# dev_kit.net
KiCad netlist of a schematic drawn in EasyEDA
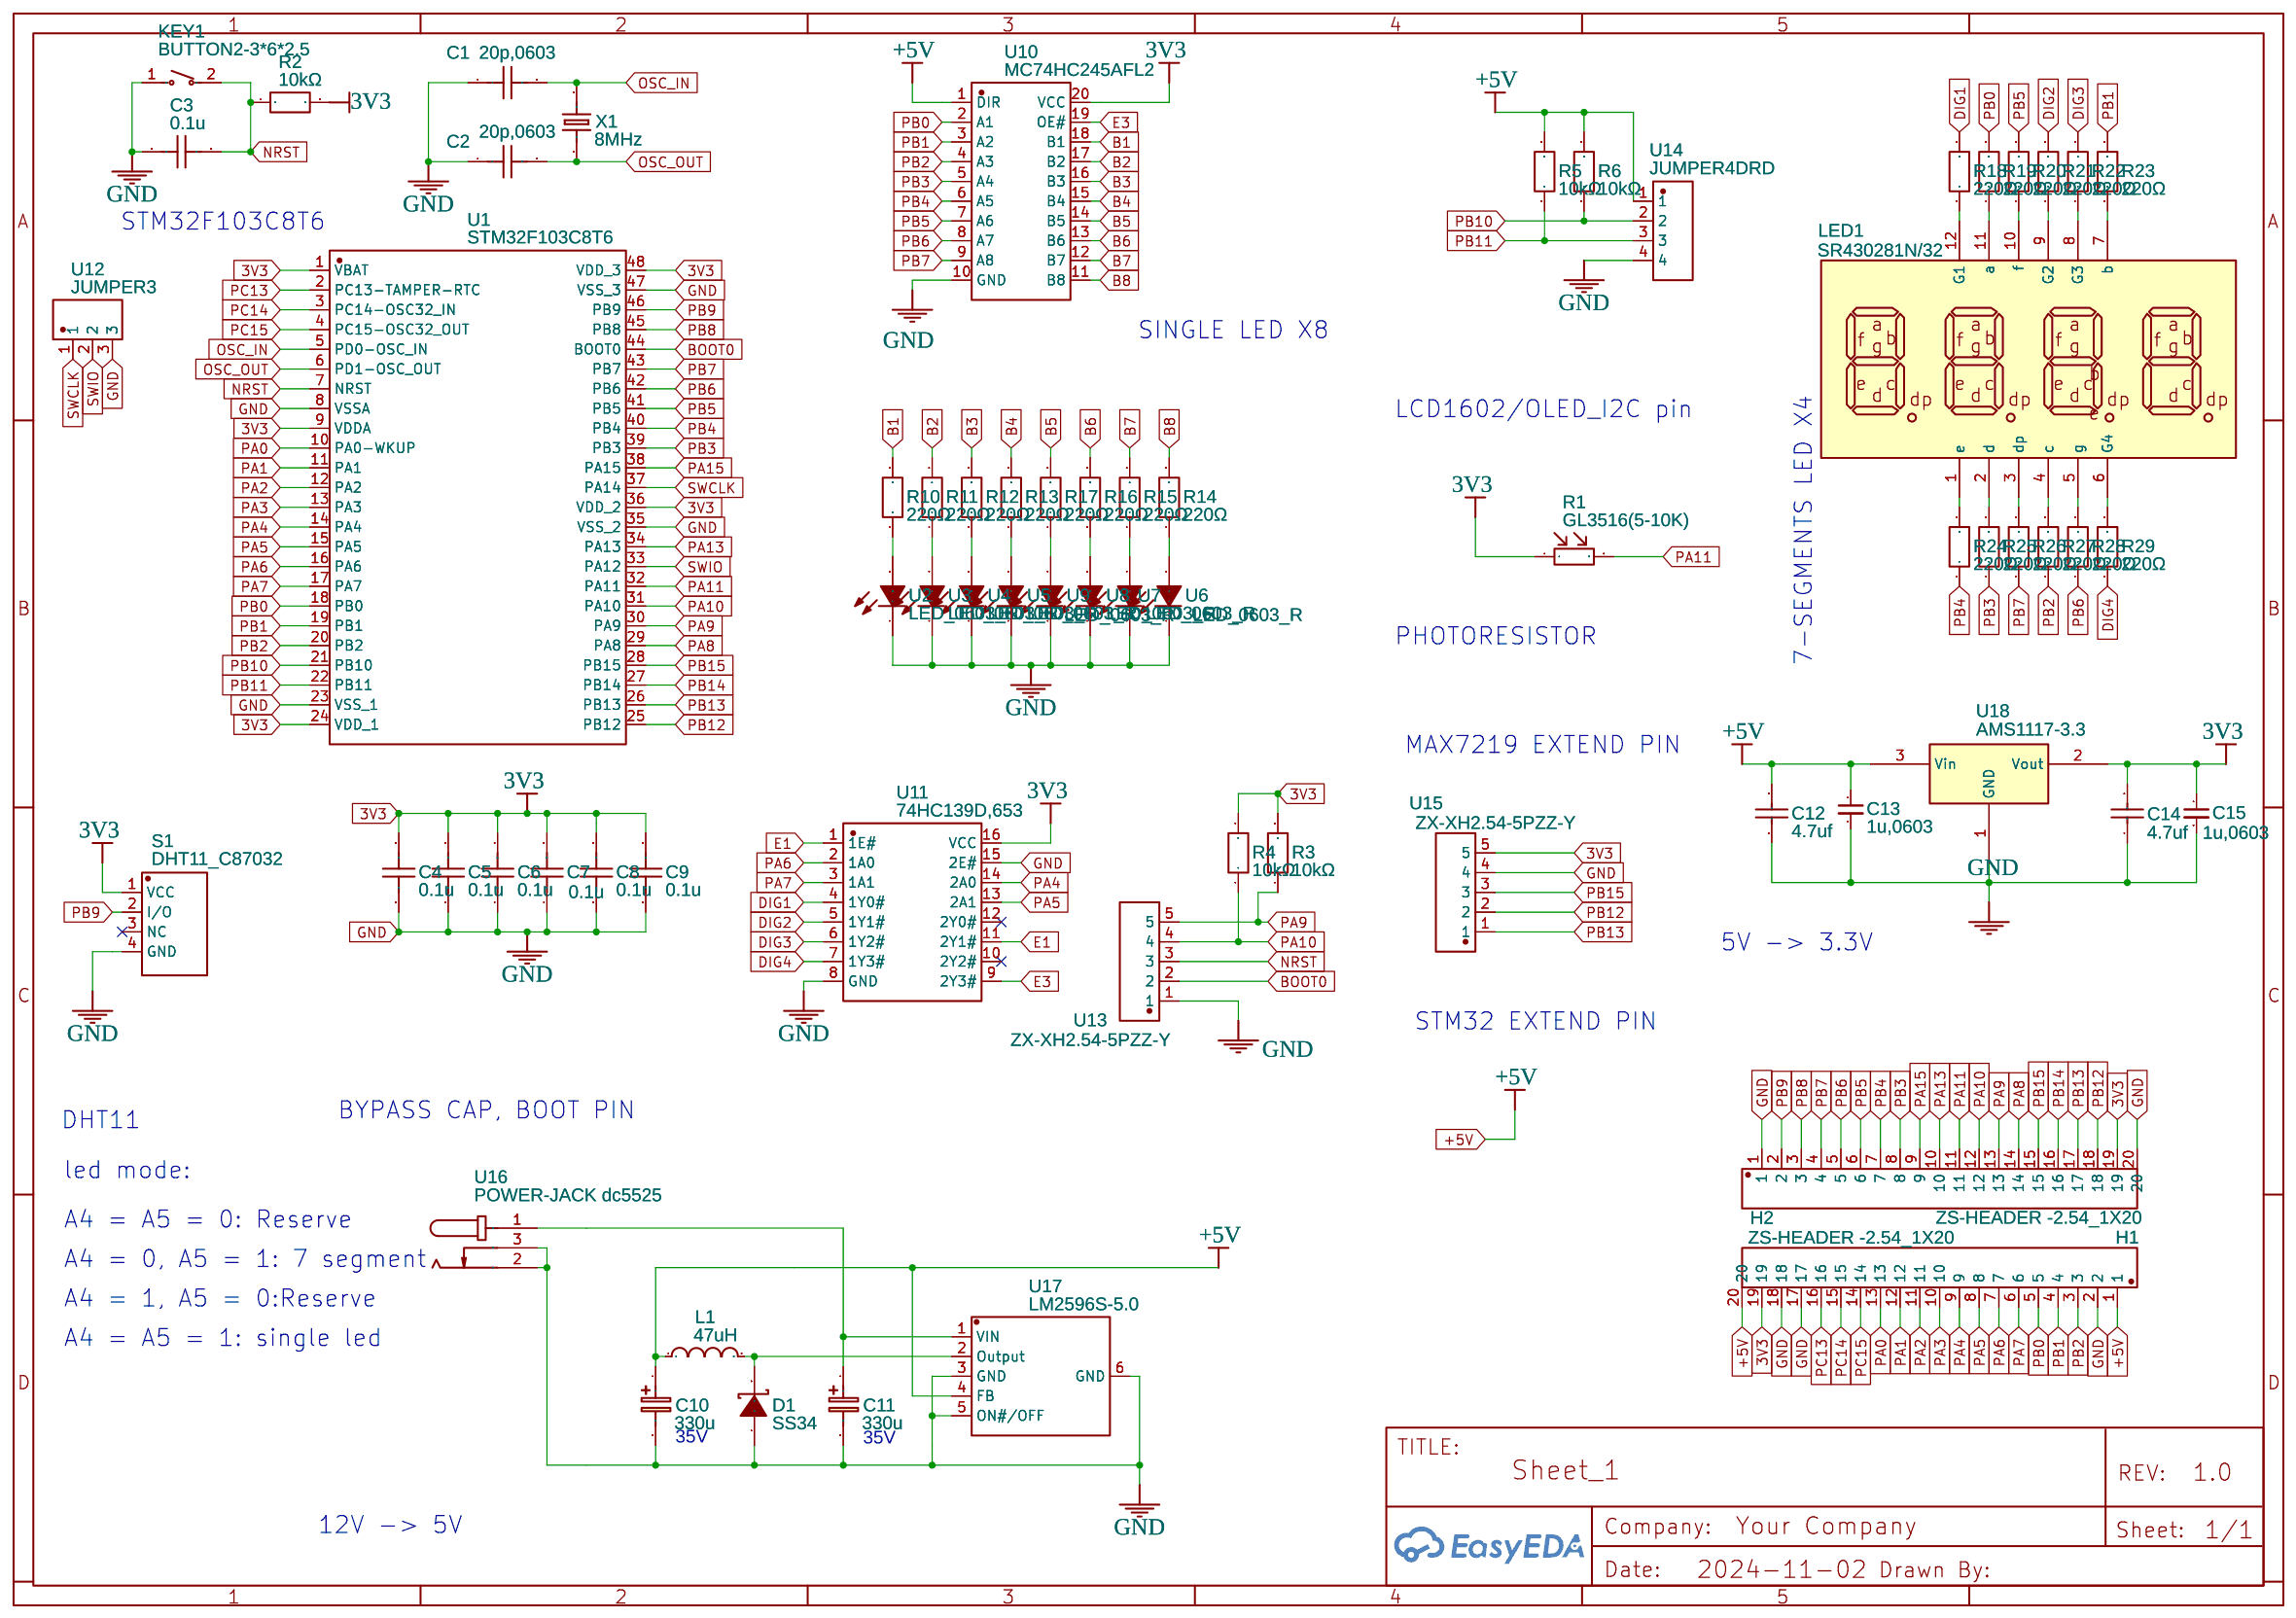
[diagram p0: schematic sheet]

(export (version "E")
  (design (tool "Eeschema 10.0.6"))
  (components
    (comp (ref "C1") (value "20p,0603") (libsource (lib "") (part "C_0603_US_1")))
    (comp (ref "C2") (value "20p,0603") (libsource (lib "") (part "C_0603_US_1")))
    (comp (ref "C3") (value "0.1u") (libsource (lib "") (part "C_0603_US_1")))
    (comp (ref "C4") (value "0.1u") (libsource (lib "") (part "C_0603_US")))
    (comp (ref "C5") (value "0.1u") (libsource (lib "") (part "C_0603_US")))
    (comp (ref "C6") (value "0.1u") (libsource (lib "") (part "C_0603_US")))
    (comp (ref "C7") (value "0.1u") (libsource (lib "") (part "C_0603_US")))
    (comp (ref "C8") (value "0.1u") (libsource (lib "") (part "C_0603_US")))
    (comp (ref "C9") (value "0.1u") (libsource (lib "") (part "C_0603_US")))
    (comp (ref "C10")
      (value "330u")
      (fields (field (name "Manufacturer Part") "?"))
      (libsource (lib "") (part "Cap_Electrolytic(SMD)_D8.0XH10.5_EU"))
    )
    (comp (ref "C11")
      (value "330u")
      (fields (field (name "Manufacturer Part") "?"))
      (libsource (lib "") (part "Cap_Electrolytic(SMD)_D8.0XH10.5_EU"))
    )
    (comp (ref "C12")
      (value "4.7uf")
      (fields (field (name "Manufacturer Part") "?"))
      (libsource (lib "") (part "Unknown_890_-400"))
    )
    (comp (ref "C13") (value "1u,0603") (libsource (lib "") (part "C_0603")))
    (comp (ref "C14")
      (value "4.7uf")
      (fields (field (name "Manufacturer Part") "?"))
      (libsource (lib "") (part "Unknown_1070_-400"))
    )
    (comp (ref "C15") (value "1u,0603") (libsource (lib "") (part "C_0603")))
    (comp (ref "D1")
      (value "SS34")
      (fields (field (name "Manufacturer") "Yenji"))
      (libsource (lib "") (part "Unknown_375_-105"))
    )
    (comp (ref "H1") (value "ZS-HEADER -2.54_1X20") (libsource (lib "") (part "ZS-HEADER -2.54_1X20")))
    (comp (ref "H2") (value "ZS-HEADER -2.54_1X20") (libsource (lib "") (part "ZS-HEADER -2.54_1X20_1")))
    (comp (ref "KEY1") (value "BUTTON2-3*6*2.5") (libsource (lib "") (part "BUTTON2-3*6*2.5")))
    (comp (ref "L1")
      (value "47uH")
      (fields (field (name "Manufacturer Part") "CDRH127NP-470MC") (field (name "Manufacturer") "Sumida"))
      (libsource (lib "") (part "CDRH127NP-470MC"))
    )
    (comp (ref "LED1")
      (value "SR430281N/32")
      (fields (field (name "Manufacturer") "ARKLED(方舟)"))
      (libsource (lib "") (part "SR430281N/32"))
    )
    (comp (ref "R1")
      (value "GL3516(5-10K)")
      (fields (field (name "Manufacturer Part") "GL3516（5-10K）") (field (name "Manufacturer") "JCHL(晶创和立)"))
      (libsource (lib "") (part "GL3516(5-10K)"))
    )
    (comp (ref "R2")
      (value "10kΩ")
      (fields (field (name "Manufacturer Part") "TD03E1002BT") (field (name "Manufacturer") "FH(风华)"))
      (libsource (lib "") (part "TD03E1002BT_1"))
    )
    (comp (ref "R3")
      (value "10kΩ")
      (fields (field (name "Manufacturer Part") "TD03E1002BT") (field (name "Manufacturer") "FH(风华)"))
      (libsource (lib "") (part "TD03E1002BT"))
    )
    (comp (ref "R4")
      (value "10kΩ")
      (fields (field (name "Manufacturer Part") "TD03E1002BT") (field (name "Manufacturer") "FH(风华)"))
      (libsource (lib "") (part "TD03E1002BT"))
    )
    (comp (ref "R5")
      (value "10kΩ")
      (fields (field (name "Manufacturer Part") "TD03E1002BT") (field (name "Manufacturer") "FH(风华)"))
      (libsource (lib "") (part "TD03E1002BT"))
    )
    (comp (ref "R6")
      (value "10kΩ")
      (fields (field (name "Manufacturer Part") "TD03E1002BT") (field (name "Manufacturer") "FH(风华)"))
      (libsource (lib "") (part "TD03E1002BT"))
    )
    (comp (ref "R10")
      (value "220Ω")
      (fields
        (field (name "Manufacturer Part") "CRCW0603220RFKEA")
        (field (name "Manufacturer") "VISHAY(威世)")
      )
      (libsource (lib "") (part "CRCW0603220RFKEA"))
    )
    (comp (ref "R11")
      (value "220Ω")
      (fields
        (field (name "Manufacturer Part") "CRCW0603220RFKEA")
        (field (name "Manufacturer") "VISHAY(威世)")
      )
      (libsource (lib "") (part "CRCW0603220RFKEA"))
    )
    (comp (ref "R12")
      (value "220Ω")
      (fields
        (field (name "Manufacturer Part") "CRCW0603220RFKEA")
        (field (name "Manufacturer") "VISHAY(威世)")
      )
      (libsource (lib "") (part "CRCW0603220RFKEA"))
    )
    (comp (ref "R13")
      (value "220Ω")
      (fields
        (field (name "Manufacturer Part") "CRCW0603220RFKEA")
        (field (name "Manufacturer") "VISHAY(威世)")
      )
      (libsource (lib "") (part "CRCW0603220RFKEA"))
    )
    (comp (ref "R14")
      (value "220Ω")
      (fields
        (field (name "Manufacturer Part") "CRCW0603220RFKEA")
        (field (name "Manufacturer") "VISHAY(威世)")
      )
      (libsource (lib "") (part "CRCW0603220RFKEA"))
    )
    (comp (ref "R15")
      (value "220Ω")
      (fields
        (field (name "Manufacturer Part") "CRCW0603220RFKEA")
        (field (name "Manufacturer") "VISHAY(威世)")
      )
      (libsource (lib "") (part "CRCW0603220RFKEA"))
    )
    (comp (ref "R16")
      (value "220Ω")
      (fields
        (field (name "Manufacturer Part") "CRCW0603220RFKEA")
        (field (name "Manufacturer") "VISHAY(威世)")
      )
      (libsource (lib "") (part "CRCW0603220RFKEA"))
    )
    (comp (ref "R17")
      (value "220Ω")
      (fields
        (field (name "Manufacturer Part") "CRCW0603220RFKEA")
        (field (name "Manufacturer") "VISHAY(威世)")
      )
      (libsource (lib "") (part "CRCW0603220RFKEA"))
    )
    (comp (ref "R18")
      (value "220Ω")
      (fields
        (field (name "Manufacturer Part") "CRCW0603220RFKEA")
        (field (name "Manufacturer") "VISHAY(威世)")
      )
      (libsource (lib "") (part "CRCW0603220RFKEA"))
    )
    (comp (ref "R19")
      (value "220Ω")
      (fields
        (field (name "Manufacturer Part") "CRCW0603220RFKEA")
        (field (name "Manufacturer") "VISHAY(威世)")
      )
      (libsource (lib "") (part "CRCW0603220RFKEA"))
    )
    (comp (ref "R20")
      (value "220Ω")
      (fields
        (field (name "Manufacturer Part") "CRCW0603220RFKEA")
        (field (name "Manufacturer") "VISHAY(威世)")
      )
      (libsource (lib "") (part "CRCW0603220RFKEA"))
    )
    (comp (ref "R21")
      (value "220Ω")
      (fields
        (field (name "Manufacturer Part") "CRCW0603220RFKEA")
        (field (name "Manufacturer") "VISHAY(威世)")
      )
      (libsource (lib "") (part "CRCW0603220RFKEA"))
    )
    (comp (ref "R22")
      (value "220Ω")
      (fields
        (field (name "Manufacturer Part") "CRCW0603220RFKEA")
        (field (name "Manufacturer") "VISHAY(威世)")
      )
      (libsource (lib "") (part "CRCW0603220RFKEA"))
    )
    (comp (ref "R23")
      (value "220Ω")
      (fields
        (field (name "Manufacturer Part") "CRCW0603220RFKEA")
        (field (name "Manufacturer") "VISHAY(威世)")
      )
      (libsource (lib "") (part "CRCW0603220RFKEA"))
    )
    (comp (ref "R24")
      (value "220Ω")
      (fields
        (field (name "Manufacturer Part") "CRCW0603220RFKEA")
        (field (name "Manufacturer") "VISHAY(威世)")
      )
      (libsource (lib "") (part "CRCW0603220RFKEA"))
    )
    (comp (ref "R25")
      (value "220Ω")
      (fields
        (field (name "Manufacturer Part") "CRCW0603220RFKEA")
        (field (name "Manufacturer") "VISHAY(威世)")
      )
      (libsource (lib "") (part "CRCW0603220RFKEA"))
    )
    (comp (ref "R26")
      (value "220Ω")
      (fields
        (field (name "Manufacturer Part") "CRCW0603220RFKEA")
        (field (name "Manufacturer") "VISHAY(威世)")
      )
      (libsource (lib "") (part "CRCW0603220RFKEA"))
    )
    (comp (ref "R27")
      (value "220Ω")
      (fields
        (field (name "Manufacturer Part") "CRCW0603220RFKEA")
        (field (name "Manufacturer") "VISHAY(威世)")
      )
      (libsource (lib "") (part "CRCW0603220RFKEA"))
    )
    (comp (ref "R28")
      (value "220Ω")
      (fields
        (field (name "Manufacturer Part") "CRCW0603220RFKEA")
        (field (name "Manufacturer") "VISHAY(威世)")
      )
      (libsource (lib "") (part "CRCW0603220RFKEA"))
    )
    (comp (ref "R29")
      (value "220Ω")
      (fields
        (field (name "Manufacturer Part") "CRCW0603220RFKEA")
        (field (name "Manufacturer") "VISHAY(威世)")
      )
      (libsource (lib "") (part "CRCW0603220RFKEA"))
    )
    (comp (ref "S1")
      (value "DHT11_C87032")
      (fields (field (name "Manufacturer Part") "DHT11") (field (name "Manufacturer") "AOSONG"))
      (libsource (lib "") (part "DHT11_C87032"))
    )
    (comp (ref "U1")
      (value "STM32F103C8T6")
      (fields (field (name "Manufacturer") "ST(意法半导体)"))
      (libsource (lib "") (part "STM32F103C8T6"))
    )
    (comp (ref "U2") (value "LED_0603_R") (libsource (lib "") (part "LED_0603_R")))
    (comp (ref "U3") (value "LED_0603_R") (libsource (lib "") (part "LED_0603_R")))
    (comp (ref "U4") (value "LED_0603_R") (libsource (lib "") (part "LED_0603_R")))
    (comp (ref "U5") (value "LED_0603_R") (libsource (lib "") (part "LED_0603_R")))
    (comp (ref "U6") (value "LED_0603_R") (libsource (lib "") (part "LED_0603_R")))
    (comp (ref "U7") (value "LED_0603_R") (libsource (lib "") (part "LED_0603_R")))
    (comp (ref "U8") (value "LED_0603_R") (libsource (lib "") (part "LED_0603_R")))
    (comp (ref "U9") (value "LED_0603_R") (libsource (lib "") (part "LED_0603_R")))
    (comp (ref "U10")
      (value "MC74HC245AFL2")
      (fields (field (name "Manufacturer") "MOTOROLA(摩托罗拉)"))
      (libsource (lib "") (part "MC74HC245AFL2"))
    )
    (comp (ref "U11")
      (value "74HC139D,653")
      (fields (field (name "Manufacturer") "Nexperia(安世)"))
      (libsource (lib "") (part "74HC139D,653"))
    )
    (comp (ref "U12")
      (value "JUMPER3")
      (fields (field (name "Manufacturer Part") "Jumper3"))
      (libsource (lib "") (part "JUMPER3"))
    )
    (comp (ref "U13")
      (value "ZX-XH2.54-5PZZ-Y")
      (fields (field (name "Manufacturer") "Megastar(兆星)"))
      (libsource (lib "") (part "ZX-XH2.54-5PZZ-Y"))
    )
    (comp (ref "U14")
      (value "JUMPER4DRD")
      (fields (field (name "Manufacturer Part") "Jumper4"))
      (libsource (lib "") (part "JUMPER4DRD"))
    )
    (comp (ref "U15")
      (value "ZX-XH2.54-5PZZ-Y")
      (fields (field (name "Manufacturer") "Megastar(兆星)"))
      (libsource (lib "") (part "ZX-XH2.54-5PZZ-Y"))
    )
    (comp (ref "U16")
      (value "POWER-JACK dc5525")
      (fields (field (name "Manufacturer Part") "POWER-JACK"))
      (libsource (lib "") (part "POWER-JACK dc5525"))
    )
    (comp (ref "U17")
      (value "LM2596S-5.0")
      (fields
        (field (name "Manufacturer Part") "LM2596S-5.0/NOPB")
        (field (name "Manufacturer") "Texas Instruments")
      )
      (libsource (lib "") (part "Unknown_520_-120"))
    )
    (comp (ref "U18")
      (value "AMS1117-3.3")
      (fields (field (name "Manufacturer Part") "?"))
      (libsource (lib "") (part "Unknown_1000_-420"))
    )
    (comp (ref "X1")
      (value "8MHz")
      (fields
        (field (name "Manufacturer Part") "49S-8.00-20-10-10/A")
        (field (name "Manufacturer") "LIMING(利明)")
      )
      (libsource (lib "") (part "49S-8.00-20-10-10/A"))
    )
  )
  (nets
    (net (code "1") (name "+5V") (class "Default")
      (node (ref "C10") (pin "1") (pinfunction "1_1") (pintype "unspecified"))
      (node (ref "C12") (pin "2") (pinfunction "2_2") (pintype "unspecified"))
      (node (ref "C13") (pin "1") (pintype "unspecified"))
      (node (ref "H2") (pin "1") (pinfunction "1_1") (pintype "unspecified"))
      (node (ref "H2") (pin "20") (pinfunction "20_20") (pintype "unspecified"))
      (node (ref "L1") (pin "1") (pinfunction "1_1") (pintype "unspecified"))
      (node (ref "R5") (pin "2") (pinfunction "2_2") (pintype "unspecified"))
      (node (ref "R6") (pin "2") (pinfunction "2_2") (pintype "unspecified"))
      (node (ref "U10") (pin "1") (pinfunction "DIR_1") (pintype "unspecified"))
      (node (ref "U14") (pin "1") (pinfunction "1_1") (pintype "unspecified"))
      (node (ref "U17") (pin "4") (pinfunction "FB_4") (pintype "unspecified"))
      (node (ref "U18") (pin "3") (pinfunction "Vin_3") (pintype "unspecified"))
    )
    (net (code "2") (name "3V3") (class "Default")
      (node (ref "C14") (pin "2") (pinfunction "2_2") (pintype "unspecified"))
      (node (ref "C15") (pin "1") (pintype "unspecified"))
      (node (ref "C4") (pin "2") (pinfunction "2_2") (pintype "unspecified"))
      (node (ref "C5") (pin "2") (pinfunction "2_2") (pintype "unspecified"))
      (node (ref "C6") (pin "2") (pinfunction "2_2") (pintype "unspecified"))
      (node (ref "C7") (pin "2") (pinfunction "2_2") (pintype "unspecified"))
      (node (ref "C8") (pin "2") (pinfunction "2_2") (pintype "unspecified"))
      (node (ref "C9") (pin "2") (pinfunction "2_2") (pintype "unspecified"))
      (node (ref "H1") (pin "19") (pinfunction "19_19") (pintype "unspecified"))
      (node (ref "H2") (pin "19") (pinfunction "19_19") (pintype "unspecified"))
      (node (ref "R1") (pin "1") (pinfunction "1_1") (pintype "input"))
      (node (ref "R2") (pin "2") (pinfunction "2_2") (pintype "unspecified"))
      (node (ref "R3") (pin "2") (pinfunction "2_2") (pintype "unspecified"))
      (node (ref "R4") (pin "2") (pinfunction "2_2") (pintype "unspecified"))
      (node (ref "S1") (pin "1") (pinfunction "VCC_1") (pintype "unspecified"))
      (node (ref "U1") (pin "1") (pinfunction "VBAT_1") (pintype "unspecified"))
      (node (ref "U1") (pin "24") (pinfunction "VDD_1_24") (pintype "unspecified"))
      (node (ref "U1") (pin "36") (pinfunction "VDD_2_36") (pintype "unspecified"))
      (node (ref "U1") (pin "48") (pinfunction "VDD_3_48") (pintype "unspecified"))
      (node (ref "U1") (pin "9") (pinfunction "VDDA_9") (pintype "unspecified"))
      (node (ref "U10") (pin "20") (pinfunction "VCC_20") (pintype "unspecified"))
      (node (ref "U11") (pin "16") (pinfunction "VCC_16") (pintype "unspecified"))
      (node (ref "U15") (pin "5") (pinfunction "5_5") (pintype "unspecified"))
      (node (ref "U18") (pin "2") (pinfunction "Vout_2") (pintype "unspecified"))
    )
    (net (code "3") (name "B1") (class "Default")
      (node (ref "R10") (pin "2") (pinfunction "2_2") (pintype "unspecified"))
      (node (ref "U10") (pin "18") (pinfunction "B1_18") (pintype "unspecified"))
    )
    (net (code "4") (name "B2") (class "Default")
      (node (ref "R11") (pin "2") (pinfunction "2_2") (pintype "unspecified"))
      (node (ref "U10") (pin "17") (pinfunction "B2_17") (pintype "unspecified"))
    )
    (net (code "5") (name "B3") (class "Default")
      (node (ref "R12") (pin "2") (pinfunction "2_2") (pintype "unspecified"))
      (node (ref "U10") (pin "16") (pinfunction "B3_16") (pintype "unspecified"))
    )
    (net (code "6") (name "B4") (class "Default")
      (node (ref "R13") (pin "2") (pinfunction "2_2") (pintype "unspecified"))
      (node (ref "U10") (pin "15") (pinfunction "B4_15") (pintype "unspecified"))
    )
    (net (code "7") (name "B5") (class "Default")
      (node (ref "R17") (pin "2") (pinfunction "2_2") (pintype "unspecified"))
      (node (ref "U10") (pin "14") (pinfunction "B5_14") (pintype "unspecified"))
    )
    (net (code "8") (name "B6") (class "Default")
      (node (ref "R16") (pin "2") (pinfunction "2_2") (pintype "unspecified"))
      (node (ref "U10") (pin "13") (pinfunction "B6_13") (pintype "unspecified"))
    )
    (net (code "9") (name "B7") (class "Default")
      (node (ref "R15") (pin "2") (pinfunction "2_2") (pintype "unspecified"))
      (node (ref "U10") (pin "12") (pinfunction "B7_12") (pintype "unspecified"))
    )
    (net (code "10") (name "B8") (class "Default")
      (node (ref "R14") (pin "2") (pinfunction "2_2") (pintype "unspecified"))
      (node (ref "U10") (pin "11") (pinfunction "B8_11") (pintype "unspecified"))
    )
    (net (code "11") (name "BOOT0") (class "Default")
      (node (ref "U1") (pin "44") (pinfunction "BOOT0_44") (pintype "unspecified"))
      (node (ref "U13") (pin "2") (pinfunction "2_2") (pintype "unspecified"))
    )
    (net (code "12") (name "DIG1") (class "Default")
      (node (ref "R18") (pin "2") (pinfunction "2_2") (pintype "unspecified"))
      (node (ref "U11") (pin "4") (pinfunction "1Y0#_4") (pintype "unspecified"))
    )
    (net (code "13") (name "DIG2") (class "Default")
      (node (ref "R21") (pin "2") (pinfunction "2_2") (pintype "unspecified"))
      (node (ref "U11") (pin "5") (pinfunction "1Y1#_5") (pintype "unspecified"))
    )
    (net (code "14") (name "DIG3") (class "Default")
      (node (ref "R22") (pin "2") (pinfunction "2_2") (pintype "unspecified"))
      (node (ref "U11") (pin "6") (pinfunction "1Y2#_6") (pintype "unspecified"))
    )
    (net (code "15") (name "DIG4") (class "Default")
      (node (ref "R29") (pin "1") (pinfunction "1_1") (pintype "unspecified"))
      (node (ref "U11") (pin "7") (pinfunction "1Y3#_7") (pintype "unspecified"))
    )
    (net (code "16") (name "E1") (class "Default")
      (node (ref "U11") (pin "1") (pinfunction "1E#_1") (pintype "unspecified"))
      (node (ref "U11") (pin "11") (pinfunction "2Y1#_11") (pintype "unspecified"))
    )
    (net (code "17") (name "E3") (class "Default")
      (node (ref "U10") (pin "19") (pinfunction "OE#_19") (pintype "unspecified"))
      (node (ref "U11") (pin "9") (pinfunction "2Y3#_9") (pintype "unspecified"))
    )
    (net (code "18") (name "GND") (class "Default")
      (node (ref "C1") (pin "1") (pinfunction "1_1") (pintype "unspecified"))
      (node (ref "C10") (pin "2") (pinfunction "2_2") (pintype "unspecified"))
      (node (ref "C11") (pin "2") (pinfunction "2_2") (pintype "unspecified"))
      (node (ref "C12") (pin "1") (pinfunction "1_1") (pintype "unspecified"))
      (node (ref "C13") (pin "2") (pintype "unspecified"))
      (node (ref "C14") (pin "1") (pinfunction "1_1") (pintype "unspecified"))
      (node (ref "C15") (pin "2") (pintype "unspecified"))
      (node (ref "C2") (pin "1") (pinfunction "1_1") (pintype "unspecified"))
      (node (ref "C3") (pin "1") (pinfunction "1_1") (pintype "unspecified"))
      (node (ref "C4") (pin "1") (pinfunction "1_1") (pintype "unspecified"))
      (node (ref "C5") (pin "1") (pinfunction "1_1") (pintype "unspecified"))
      (node (ref "C6") (pin "1") (pinfunction "1_1") (pintype "unspecified"))
      (node (ref "C7") (pin "1") (pinfunction "1_1") (pintype "unspecified"))
      (node (ref "C8") (pin "1") (pinfunction "1_1") (pintype "unspecified"))
      (node (ref "C9") (pin "1") (pinfunction "1_1") (pintype "unspecified"))
      (node (ref "D1") (pin "1") (pinfunction "A_1") (pintype "unspecified"))
      (node (ref "H1") (pin "1") (pinfunction "1_1") (pintype "unspecified"))
      (node (ref "H1") (pin "20") (pinfunction "20_20") (pintype "unspecified"))
      (node (ref "H2") (pin "17") (pinfunction "17_17") (pintype "unspecified"))
      (node (ref "H2") (pin "18") (pinfunction "18_18") (pintype "unspecified"))
      (node (ref "H2") (pin "2") (pinfunction "2_2") (pintype "unspecified"))
      (node (ref "KEY1") (pin "1") (pinfunction "1_1") (pintype "unspecified"))
      (node (ref "S1") (pin "4") (pinfunction "GND_4") (pintype "unspecified"))
      (node (ref "U1") (pin "23") (pinfunction "VSS_1_23") (pintype "unspecified"))
      (node (ref "U1") (pin "35") (pinfunction "VSS_2_35") (pintype "unspecified"))
      (node (ref "U1") (pin "47") (pinfunction "VSS_3_47") (pintype "unspecified"))
      (node (ref "U1") (pin "8") (pinfunction "VSSA_8") (pintype "unspecified"))
      (node (ref "U10") (pin "10") (pinfunction "GND_10") (pintype "unspecified"))
      (node (ref "U11") (pin "15") (pinfunction "2E#_15") (pintype "unspecified"))
      (node (ref "U11") (pin "8") (pinfunction "GND_8") (pintype "unspecified"))
      (node (ref "U12") (pin "3") (pinfunction "3_3") (pintype "unspecified"))
      (node (ref "U13") (pin "1") (pinfunction "1_1") (pintype "unspecified"))
      (node (ref "U14") (pin "4") (pinfunction "4_4") (pintype "unspecified"))
      (node (ref "U15") (pin "4") (pinfunction "4_4") (pintype "unspecified"))
      (node (ref "U16") (pin "2") (pinfunction "2_2") (pintype "unspecified"))
      (node (ref "U16") (pin "3") (pinfunction "3_3") (pintype "unspecified"))
      (node (ref "U17") (pin "3") (pinfunction "GND_3") (pintype "unspecified"))
      (node (ref "U17") (pin "5") (pinfunction "ON#/OFF_5") (pintype "unspecified"))
      (node (ref "U17") (pin "6") (pinfunction "GND_6") (pintype "unspecified"))
      (node (ref "U18") (pin "1") (pinfunction "GND_1") (pintype "unspecified"))
      (node (ref "U2") (pin "1") (pinfunction "-_1") (pintype "input"))
      (node (ref "U3") (pin "1") (pinfunction "-_1") (pintype "input"))
      (node (ref "U4") (pin "1") (pinfunction "-_1") (pintype "input"))
      (node (ref "U5") (pin "1") (pinfunction "-_1") (pintype "input"))
      (node (ref "U6") (pin "1") (pinfunction "-_1") (pintype "input"))
      (node (ref "U7") (pin "1") (pinfunction "-_1") (pintype "input"))
      (node (ref "U8") (pin "1") (pinfunction "-_1") (pintype "input"))
      (node (ref "U9") (pin "1") (pinfunction "-_1") (pintype "input"))
    )
    (net (code "19") (name "NRST") (class "Default")
      (node (ref "C3") (pin "2") (pinfunction "2_2") (pintype "unspecified"))
      (node (ref "KEY1") (pin "2") (pinfunction "2_2") (pintype "unspecified"))
      (node (ref "R2") (pin "1") (pinfunction "1_1") (pintype "unspecified"))
      (node (ref "U1") (pin "7") (pinfunction "NRST_7") (pintype "unspecified"))
      (node (ref "U13") (pin "3") (pinfunction "3_3") (pintype "unspecified"))
    )
    (net (code "20") (name "Net-(D1-K)") (class "Default")
      (node (ref "D1") (pin "2") (pinfunction "K_2") (pintype "unspecified"))
      (node (ref "L1") (pin "2") (pinfunction "2_2") (pintype "unspecified"))
      (node (ref "U17") (pin "2") (pinfunction "Output_2") (pintype "unspecified"))
    )
    (net (code "21") (name "Net-(LED1-G1)") (class "Default")
      (node (ref "LED1") (pin "12") (pinfunction "G1_12") (pintype "input"))
      (node (ref "R18") (pin "1") (pinfunction "1_1") (pintype "unspecified"))
    )
    (net (code "22") (name "Net-(LED1-G2)") (class "Default")
      (node (ref "LED1") (pin "9") (pinfunction "G2_9") (pintype "input"))
      (node (ref "R21") (pin "1") (pinfunction "1_1") (pintype "unspecified"))
    )
    (net (code "23") (name "Net-(LED1-G3)") (class "Default")
      (node (ref "LED1") (pin "8") (pinfunction "G3_8") (pintype "input"))
      (node (ref "R22") (pin "1") (pinfunction "1_1") (pintype "unspecified"))
    )
    (net (code "24") (name "Net-(LED1-G4)") (class "Default")
      (node (ref "LED1") (pin "6") (pinfunction "G4_6") (pintype "input"))
      (node (ref "R29") (pin "2") (pinfunction "2_2") (pintype "unspecified"))
    )
    (net (code "25") (name "Net-(LED1-a)") (class "Default")
      (node (ref "LED1") (pin "11") (pinfunction "a_11") (pintype "input"))
      (node (ref "R19") (pin "1") (pinfunction "1_1") (pintype "unspecified"))
    )
    (net (code "26") (name "Net-(LED1-b)") (class "Default")
      (node (ref "LED1") (pin "7") (pinfunction "b_7") (pintype "input"))
      (node (ref "R23") (pin "1") (pinfunction "1_1") (pintype "unspecified"))
    )
    (net (code "27") (name "Net-(LED1-c)") (class "Default")
      (node (ref "LED1") (pin "4") (pinfunction "c_4") (pintype "input"))
      (node (ref "R27") (pin "2") (pinfunction "2_2") (pintype "unspecified"))
    )
    (net (code "28") (name "Net-(LED1-d)") (class "Default")
      (node (ref "LED1") (pin "2") (pinfunction "d_2") (pintype "input"))
      (node (ref "R25") (pin "2") (pinfunction "2_2") (pintype "unspecified"))
    )
    (net (code "29") (name "Net-(LED1-dp)") (class "Default")
      (node (ref "LED1") (pin "3") (pinfunction "dp_3") (pintype "input"))
      (node (ref "R26") (pin "2") (pinfunction "2_2") (pintype "unspecified"))
    )
    (net (code "30") (name "Net-(LED1-e)") (class "Default")
      (node (ref "LED1") (pin "1") (pinfunction "e_1") (pintype "input"))
      (node (ref "R24") (pin "2") (pinfunction "2_2") (pintype "unspecified"))
    )
    (net (code "31") (name "Net-(LED1-f)") (class "Default")
      (node (ref "LED1") (pin "10") (pinfunction "f_10") (pintype "input"))
      (node (ref "R20") (pin "1") (pinfunction "1_1") (pintype "unspecified"))
    )
    (net (code "32") (name "Net-(LED1-g)") (class "Default")
      (node (ref "LED1") (pin "5") (pinfunction "g_5") (pintype "input"))
      (node (ref "R28") (pin "2") (pinfunction "2_2") (pintype "unspecified"))
    )
    (net (code "33") (name "Net-(U2-+)") (class "Default")
      (node (ref "R10") (pin "1") (pinfunction "1_1") (pintype "unspecified"))
      (node (ref "U2") (pin "2") (pinfunction "+_2") (pintype "input"))
    )
    (net (code "34") (name "Net-(U3-+)") (class "Default")
      (node (ref "R11") (pin "1") (pinfunction "1_1") (pintype "unspecified"))
      (node (ref "U3") (pin "2") (pinfunction "+_2") (pintype "input"))
    )
    (net (code "35") (name "Net-(U4-+)") (class "Default")
      (node (ref "R12") (pin "1") (pinfunction "1_1") (pintype "unspecified"))
      (node (ref "U4") (pin "2") (pinfunction "+_2") (pintype "input"))
    )
    (net (code "36") (name "Net-(U5-+)") (class "Default")
      (node (ref "R13") (pin "1") (pinfunction "1_1") (pintype "unspecified"))
      (node (ref "U5") (pin "2") (pinfunction "+_2") (pintype "input"))
    )
    (net (code "37") (name "Net-(U6-+)") (class "Default")
      (node (ref "R14") (pin "1") (pinfunction "1_1") (pintype "unspecified"))
      (node (ref "U6") (pin "2") (pinfunction "+_2") (pintype "input"))
    )
    (net (code "38") (name "Net-(U7-+)") (class "Default")
      (node (ref "R15") (pin "1") (pinfunction "1_1") (pintype "unspecified"))
      (node (ref "U7") (pin "2") (pinfunction "+_2") (pintype "input"))
    )
    (net (code "39") (name "Net-(U8-+)") (class "Default")
      (node (ref "R16") (pin "1") (pinfunction "1_1") (pintype "unspecified"))
      (node (ref "U8") (pin "2") (pinfunction "+_2") (pintype "input"))
    )
    (net (code "40") (name "Net-(U9-+)") (class "Default")
      (node (ref "R17") (pin "1") (pinfunction "1_1") (pintype "unspecified"))
      (node (ref "U9") (pin "2") (pinfunction "+_2") (pintype "input"))
    )
    (net (code "41") (name "Net-(U17-VIN)") (class "Default")
      (node (ref "C11") (pin "1") (pinfunction "1_1") (pintype "unspecified"))
      (node (ref "U16") (pin "1") (pinfunction "1_1") (pintype "unspecified"))
      (node (ref "U17") (pin "1") (pinfunction "VIN_1") (pintype "unspecified"))
    )
    (net (code "42") (name "OSC_IN") (class "Default")
      (node (ref "C1") (pin "2") (pinfunction "2_2") (pintype "unspecified"))
      (node (ref "U1") (pin "5") (pinfunction "PD0-OSC_IN_5") (pintype "unspecified"))
      (node (ref "X1") (pin "2") (pinfunction "2_2") (pintype "unspecified"))
    )
    (net (code "43") (name "OSC_OUT") (class "Default")
      (node (ref "C2") (pin "2") (pinfunction "2_2") (pintype "unspecified"))
      (node (ref "U1") (pin "6") (pinfunction "PD1-OSC_OUT_6") (pintype "unspecified"))
      (node (ref "X1") (pin "1") (pinfunction "1_1") (pintype "unspecified"))
    )
    (net (code "44") (name "PA0") (class "Default")
      (node (ref "H2") (pin "13") (pinfunction "13_13") (pintype "unspecified"))
      (node (ref "U1") (pin "10") (pinfunction "PA0-WKUP_10") (pintype "unspecified"))
    )
    (net (code "45") (name "PA1") (class "Default")
      (node (ref "H2") (pin "12") (pinfunction "12_12") (pintype "unspecified"))
      (node (ref "U1") (pin "11") (pinfunction "PA1_11") (pintype "unspecified"))
    )
    (net (code "46") (name "PA2") (class "Default")
      (node (ref "H2") (pin "11") (pinfunction "11_11") (pintype "unspecified"))
      (node (ref "U1") (pin "12") (pinfunction "PA2_12") (pintype "unspecified"))
    )
    (net (code "47") (name "PA3") (class "Default")
      (node (ref "H2") (pin "10") (pinfunction "10_10") (pintype "unspecified"))
      (node (ref "U1") (pin "13") (pinfunction "PA3_13") (pintype "unspecified"))
    )
    (net (code "48") (name "PA4") (class "Default")
      (node (ref "H2") (pin "9") (pinfunction "9_9") (pintype "unspecified"))
      (node (ref "U1") (pin "14") (pinfunction "PA4_14") (pintype "unspecified"))
      (node (ref "U11") (pin "14") (pinfunction "2A0_14") (pintype "unspecified"))
    )
    (net (code "49") (name "PA5") (class "Default")
      (node (ref "H2") (pin "8") (pinfunction "8_8") (pintype "unspecified"))
      (node (ref "U1") (pin "15") (pinfunction "PA5_15") (pintype "unspecified"))
      (node (ref "U11") (pin "13") (pinfunction "2A1_13") (pintype "unspecified"))
    )
    (net (code "50") (name "PA6") (class "Default")
      (node (ref "H2") (pin "7") (pinfunction "7_7") (pintype "unspecified"))
      (node (ref "U1") (pin "16") (pinfunction "PA6_16") (pintype "unspecified"))
      (node (ref "U11") (pin "2") (pinfunction "1A0_2") (pintype "unspecified"))
    )
    (net (code "51") (name "PA7") (class "Default")
      (node (ref "H2") (pin "6") (pinfunction "6_6") (pintype "unspecified"))
      (node (ref "U1") (pin "17") (pinfunction "PA7_17") (pintype "unspecified"))
      (node (ref "U11") (pin "3") (pinfunction "1A1_3") (pintype "unspecified"))
    )
    (net (code "52") (name "PA8") (class "Default")
      (node (ref "H1") (pin "14") (pinfunction "14_14") (pintype "unspecified"))
      (node (ref "U1") (pin "29") (pinfunction "PA8_29") (pintype "unspecified"))
    )
    (net (code "53") (name "PA9") (class "Default")
      (node (ref "H1") (pin "13") (pinfunction "13_13") (pintype "unspecified"))
      (node (ref "R3") (pin "1") (pinfunction "1_1") (pintype "unspecified"))
      (node (ref "U1") (pin "30") (pinfunction "PA9_30") (pintype "unspecified"))
      (node (ref "U13") (pin "5") (pinfunction "5_5") (pintype "unspecified"))
    )
    (net (code "54") (name "PA10") (class "Default")
      (node (ref "H1") (pin "12") (pinfunction "12_12") (pintype "unspecified"))
      (node (ref "R4") (pin "1") (pinfunction "1_1") (pintype "unspecified"))
      (node (ref "U1") (pin "31") (pinfunction "PA10_31") (pintype "unspecified"))
      (node (ref "U13") (pin "4") (pinfunction "4_4") (pintype "unspecified"))
    )
    (net (code "55") (name "PA11") (class "Default")
      (node (ref "H1") (pin "11") (pinfunction "11_11") (pintype "unspecified"))
      (node (ref "R1") (pin "2") (pinfunction "2_2") (pintype "input"))
      (node (ref "U1") (pin "32") (pinfunction "PA11_32") (pintype "unspecified"))
    )
    (net (code "56") (name "PA13") (class "Default")
      (node (ref "H1") (pin "10") (pinfunction "10_10") (pintype "unspecified"))
      (node (ref "U1") (pin "34") (pinfunction "PA13_34") (pintype "unspecified"))
    )
    (net (code "57") (name "PA15") (class "Default")
      (node (ref "H1") (pin "9") (pinfunction "9_9") (pintype "unspecified"))
      (node (ref "U1") (pin "38") (pinfunction "PA15_38") (pintype "unspecified"))
    )
    (net (code "58") (name "PB0") (class "Default")
      (node (ref "H2") (pin "5") (pinfunction "5_5") (pintype "unspecified"))
      (node (ref "R19") (pin "2") (pinfunction "2_2") (pintype "unspecified"))
      (node (ref "U1") (pin "18") (pinfunction "PB0_18") (pintype "unspecified"))
      (node (ref "U10") (pin "2") (pinfunction "A1_2") (pintype "unspecified"))
    )
    (net (code "59") (name "PB1") (class "Default")
      (node (ref "H2") (pin "4") (pinfunction "4_4") (pintype "unspecified"))
      (node (ref "R23") (pin "2") (pinfunction "2_2") (pintype "unspecified"))
      (node (ref "U1") (pin "19") (pinfunction "PB1_19") (pintype "unspecified"))
      (node (ref "U10") (pin "3") (pinfunction "A2_3") (pintype "unspecified"))
    )
    (net (code "60") (name "PB2") (class "Default")
      (node (ref "H2") (pin "3") (pinfunction "3_3") (pintype "unspecified"))
      (node (ref "R27") (pin "1") (pinfunction "1_1") (pintype "unspecified"))
      (node (ref "U1") (pin "20") (pinfunction "PB2_20") (pintype "unspecified"))
      (node (ref "U10") (pin "4") (pinfunction "A3_4") (pintype "unspecified"))
    )
    (net (code "61") (name "PB3") (class "Default")
      (node (ref "H1") (pin "8") (pinfunction "8_8") (pintype "unspecified"))
      (node (ref "R25") (pin "1") (pinfunction "1_1") (pintype "unspecified"))
      (node (ref "U1") (pin "39") (pinfunction "PB3_39") (pintype "unspecified"))
      (node (ref "U10") (pin "5") (pinfunction "A4_5") (pintype "unspecified"))
    )
    (net (code "62") (name "PB4") (class "Default")
      (node (ref "H1") (pin "7") (pinfunction "7_7") (pintype "unspecified"))
      (node (ref "R24") (pin "1") (pinfunction "1_1") (pintype "unspecified"))
      (node (ref "U1") (pin "40") (pinfunction "PB4_40") (pintype "unspecified"))
      (node (ref "U10") (pin "6") (pinfunction "A5_6") (pintype "unspecified"))
    )
    (net (code "63") (name "PB5") (class "Default")
      (node (ref "H1") (pin "6") (pinfunction "6_6") (pintype "unspecified"))
      (node (ref "R20") (pin "2") (pinfunction "2_2") (pintype "unspecified"))
      (node (ref "U1") (pin "41") (pinfunction "PB5_41") (pintype "unspecified"))
      (node (ref "U10") (pin "7") (pinfunction "A6_7") (pintype "unspecified"))
    )
    (net (code "64") (name "PB6") (class "Default")
      (node (ref "H1") (pin "5") (pinfunction "5_5") (pintype "unspecified"))
      (node (ref "R28") (pin "1") (pinfunction "1_1") (pintype "unspecified"))
      (node (ref "U1") (pin "42") (pinfunction "PB6_42") (pintype "unspecified"))
      (node (ref "U10") (pin "8") (pinfunction "A7_8") (pintype "unspecified"))
    )
    (net (code "65") (name "PB7") (class "Default")
      (node (ref "H1") (pin "4") (pinfunction "4_4") (pintype "unspecified"))
      (node (ref "R26") (pin "1") (pinfunction "1_1") (pintype "unspecified"))
      (node (ref "U1") (pin "43") (pinfunction "PB7_43") (pintype "unspecified"))
      (node (ref "U10") (pin "9") (pinfunction "A8_9") (pintype "unspecified"))
    )
    (net (code "66") (name "PB8") (class "Default")
      (node (ref "H1") (pin "3") (pinfunction "3_3") (pintype "unspecified"))
      (node (ref "U1") (pin "45") (pinfunction "PB8_45") (pintype "unspecified"))
    )
    (net (code "67") (name "PB9") (class "Default")
      (node (ref "H1") (pin "2") (pinfunction "2_2") (pintype "unspecified"))
      (node (ref "S1") (pin "2") (pinfunction "I/O_2") (pintype "unspecified"))
      (node (ref "U1") (pin "46") (pinfunction "PB9_46") (pintype "unspecified"))
    )
    (net (code "68") (name "PB10") (class "Default")
      (node (ref "R6") (pin "1") (pinfunction "1_1") (pintype "unspecified"))
      (node (ref "U1") (pin "21") (pinfunction "PB10_21") (pintype "unspecified"))
      (node (ref "U14") (pin "2") (pinfunction "2_2") (pintype "unspecified"))
    )
    (net (code "69") (name "PB11") (class "Default")
      (node (ref "R5") (pin "1") (pinfunction "1_1") (pintype "unspecified"))
      (node (ref "U1") (pin "22") (pinfunction "PB11_22") (pintype "unspecified"))
      (node (ref "U14") (pin "3") (pinfunction "3_3") (pintype "unspecified"))
    )
    (net (code "70") (name "PB12") (class "Default")
      (node (ref "H1") (pin "18") (pinfunction "18_18") (pintype "unspecified"))
      (node (ref "U1") (pin "25") (pinfunction "PB12_25") (pintype "unspecified"))
      (node (ref "U15") (pin "2") (pinfunction "2_2") (pintype "unspecified"))
    )
    (net (code "71") (name "PB13") (class "Default")
      (node (ref "H1") (pin "17") (pinfunction "17_17") (pintype "unspecified"))
      (node (ref "U1") (pin "26") (pinfunction "PB13_26") (pintype "unspecified"))
      (node (ref "U15") (pin "1") (pinfunction "1_1") (pintype "unspecified"))
    )
    (net (code "72") (name "PB14") (class "Default")
      (node (ref "H1") (pin "16") (pinfunction "16_16") (pintype "unspecified"))
      (node (ref "U1") (pin "27") (pinfunction "PB14_27") (pintype "unspecified"))
    )
    (net (code "73") (name "PB15") (class "Default")
      (node (ref "H1") (pin "15") (pinfunction "15_15") (pintype "unspecified"))
      (node (ref "U1") (pin "28") (pinfunction "PB15_28") (pintype "unspecified"))
      (node (ref "U15") (pin "3") (pinfunction "3_3") (pintype "unspecified"))
    )
    (net (code "74") (name "PC13") (class "Default")
      (node (ref "H2") (pin "16") (pinfunction "16_16") (pintype "unspecified"))
      (node (ref "U1") (pin "2") (pinfunction "PC13-TAMPER-RTC_2") (pintype "unspecified"))
    )
    (net (code "75") (name "PC14") (class "Default")
      (node (ref "H2") (pin "15") (pinfunction "15_15") (pintype "unspecified"))
      (node (ref "U1") (pin "3") (pinfunction "PC14-OSC32_IN_3") (pintype "unspecified"))
    )
    (net (code "76") (name "PC15") (class "Default")
      (node (ref "H2") (pin "14") (pinfunction "14_14") (pintype "unspecified"))
      (node (ref "U1") (pin "4") (pinfunction "PC15-OSC32_OUT_4") (pintype "unspecified"))
    )
    (net (code "77") (name "SWCLK") (class "Default")
      (node (ref "U1") (pin "37") (pinfunction "PA14_37") (pintype "unspecified"))
      (node (ref "U12") (pin "1") (pinfunction "1_1") (pintype "unspecified"))
    )
    (net (code "78") (name "SWIO") (class "Default")
      (node (ref "U1") (pin "33") (pinfunction "PA12_33") (pintype "unspecified"))
      (node (ref "U12") (pin "2") (pinfunction "2_2") (pintype "unspecified"))
    )
    (net (code "79") (name "unconnected-(S1-NC-Pad3)") (class "Default")
      (node (ref "S1") (pin "3") (pinfunction "NC_3") (pintype "unspecified+no_connect"))
    )
    (net (code "80") (name "unconnected-(U11-2Y0#-Pad12)") (class "Default")
      (node (ref "U11") (pin "12") (pinfunction "2Y0#_12") (pintype "unspecified+no_connect"))
    )
    (net (code "81") (name "unconnected-(U11-2Y2#-Pad10)") (class "Default")
      (node (ref "U11") (pin "10") (pinfunction "2Y2#_10") (pintype "unspecified+no_connect"))
    )
  )
)
